# parksharks_board.net
KiCad netlist of a schematic drawn in EAGLE
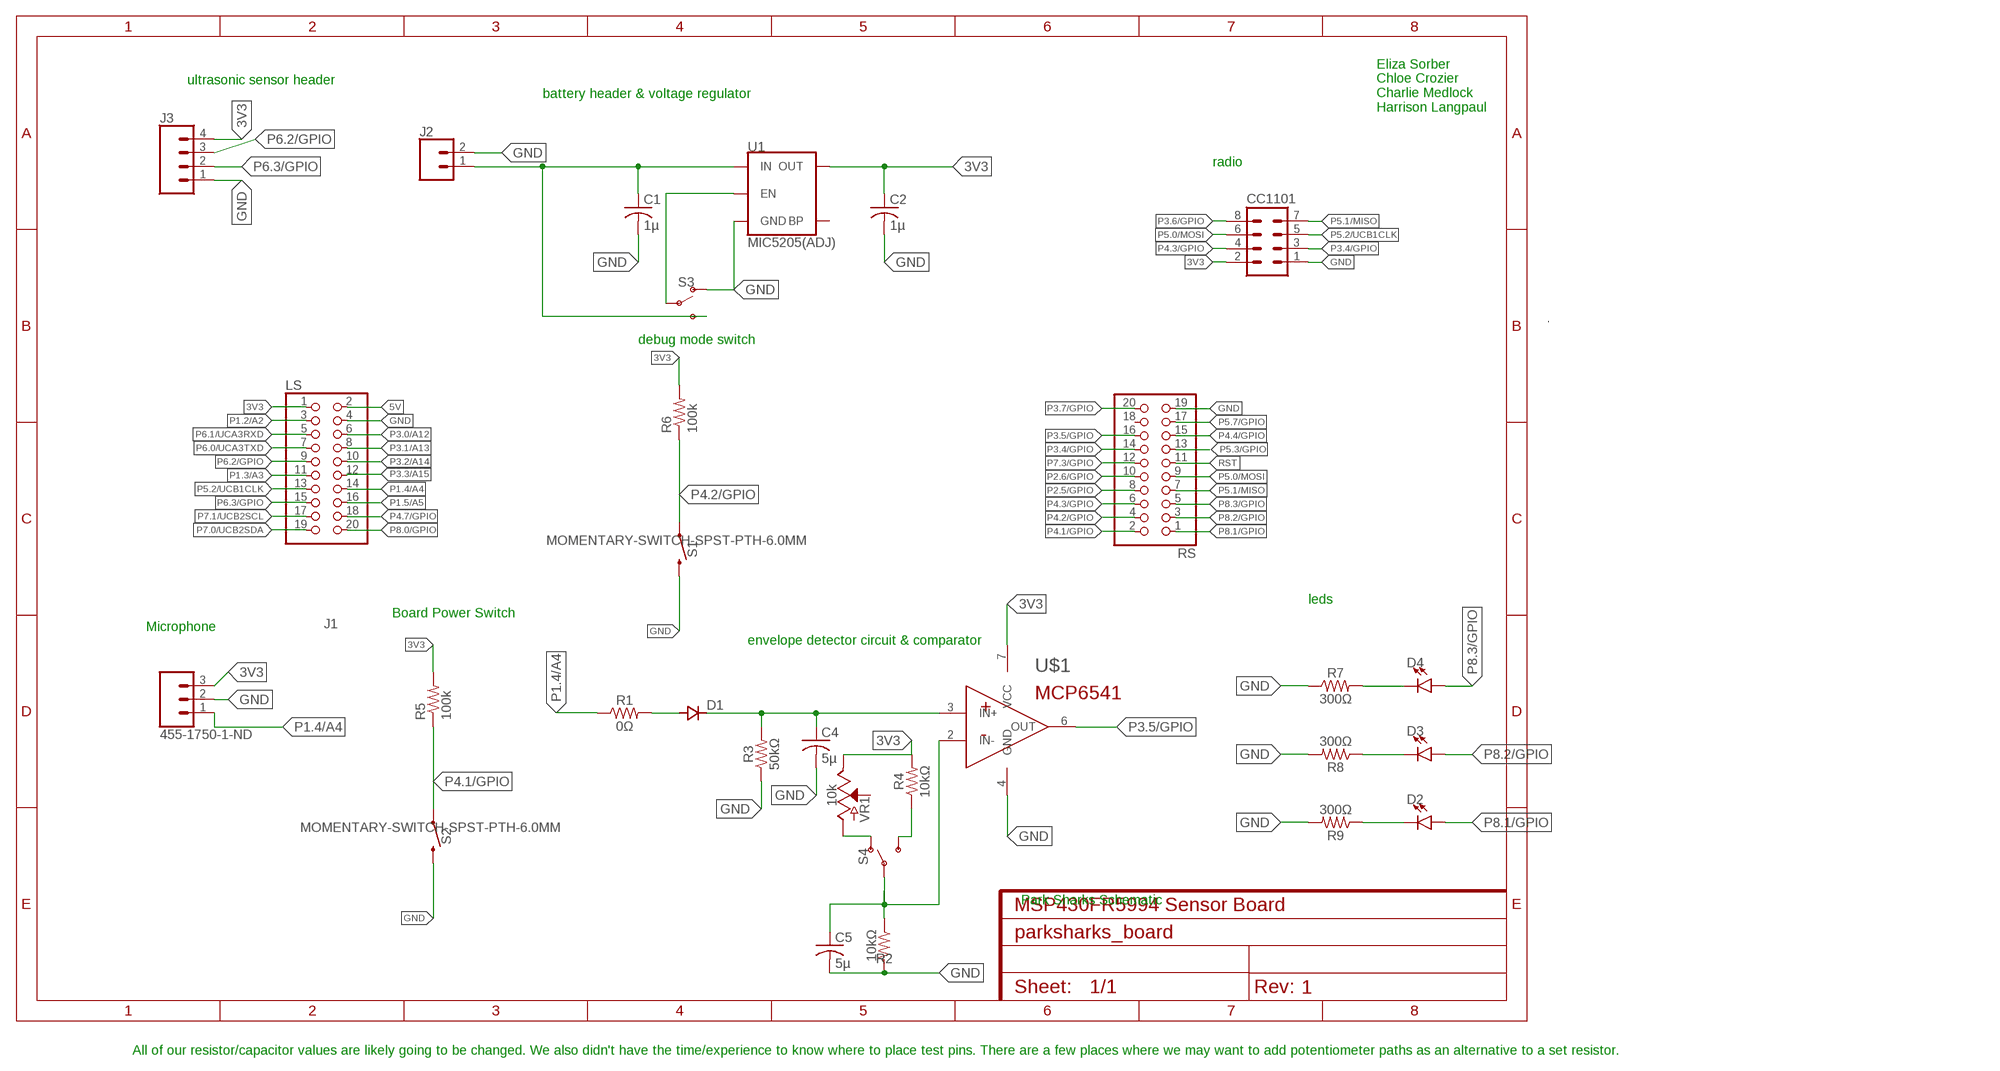
[diagram p0: schematic, sheet 1]

(export (version "E")
  (design (tool "Eeschema 10.0.6"))
  (components
    (comp (ref "C1")
      (value "1µ")
      (footprint "eagle-import:C0805")
      (libsource (lib "eagle-import") (part "C-USC0805"))
    )
    (comp (ref "C2")
      (value "1µ")
      (footprint "eagle-import:C0805")
      (libsource (lib "eagle-import") (part "C-USC0805"))
    )
    (comp (ref "C4")
      (value "5µ")
      (footprint "eagle-import:C0805")
      (libsource (lib "eagle-import") (part "C-USC0805"))
    )
    (comp (ref "C5")
      (value "5µ")
      (footprint "eagle-import:C0805")
      (libsource (lib "eagle-import") (part "C-USC0805"))
    )
    (comp (ref "CC1101")
      (value "MA04-2")
      (footprint "eagle-import:MA04-2")
      (libsource (lib "eagle-import") (part "MA04-2"))
    )
    (comp (ref "D1")
      (value "DSOD323")
      (footprint "eagle-import:SOD323")
      (fields (field (name "MPN") "CDSOD323-T05C"))
      (libsource (lib "eagle-import") (part "DSOD323"))
    )
    (comp (ref "D2")
      (value "LED5MM")
      (footprint "eagle-import:LED_5MM")
      (libsource (lib "eagle-import") (part "LED5MM"))
    )
    (comp (ref "D3")
      (value "LED5MM")
      (footprint "eagle-import:LED_5MM")
      (libsource (lib "eagle-import") (part "LED5MM"))
    )
    (comp (ref "D4")
      (value "LED5MM")
      (footprint "eagle-import:LED_5MM")
      (libsource (lib "eagle-import") (part "LED5MM"))
    )
    (comp (ref "J1")
      (value "455-1750-1-ND")
      (footprint "eagle-import:1X03")
      (libsource (lib "eagle-import") (part "CONN_03"))
    )
    (comp (ref "J2")
      (value "CONN_02")
      (footprint "eagle-import:1X02")
      (libsource (lib "eagle-import") (part "CONN_02"))
    )
    (comp (ref "J3")
      (value "CONN_04JST-PTH")
      (footprint "eagle-import:JST-4-PTH")
      (libsource (lib "eagle-import") (part "CONN_04JST-PTH"))
    )
    (comp (ref "LS")
      (value "PINHD-2X10")
      (footprint "eagle-import:2X10")
      (libsource (lib "eagle-import") (part "PINHD-2X10"))
    )
    (comp (ref "R1")
      (value "0Ω")
      (footprint "eagle-import:0805")
      (libsource (lib "eagle-import") (part "0.3OHM-0805-1/8W-1%"))
    )
    (comp (ref "R2")
      (value "10kΩ")
      (footprint "eagle-import:0805")
      (libsource (lib "eagle-import") (part "0.3OHM-0805-1/8W-1%"))
    )
    (comp (ref "R3")
      (value "50kΩ")
      (footprint "eagle-import:0805")
      (libsource (lib "eagle-import") (part "0.3OHM-0805-1/8W-1%"))
    )
    (comp (ref "R4")
      (value "10kΩ")
      (footprint "eagle-import:0805")
      (libsource (lib "eagle-import") (part "0.3OHM-0805-1/8W-1%"))
    )
    (comp (ref "R5")
      (value "100k")
      (footprint "eagle-import:R0805")
      (libsource (lib "eagle-import") (part "R-US_R0805"))
    )
    (comp (ref "R6")
      (value "100k")
      (footprint "eagle-import:R0805")
      (libsource (lib "eagle-import") (part "R-US_R0805"))
    )
    (comp (ref "R7")
      (value "300Ω")
      (footprint "eagle-import:0805")
      (libsource (lib "eagle-import") (part "0.3OHM-0805-1/8W-1%"))
    )
    (comp (ref "R8")
      (value "300Ω")
      (footprint "eagle-import:0805")
      (libsource (lib "eagle-import") (part "0.3OHM-0805-1/8W-1%"))
    )
    (comp (ref "R9")
      (value "300Ω")
      (footprint "eagle-import:0805")
      (libsource (lib "eagle-import") (part "0.3OHM-0805-1/8W-1%"))
    )
    (comp (ref "RS")
      (value "PINHD-2X10")
      (footprint "eagle-import:2X10")
      (libsource (lib "eagle-import") (part "PINHD-2X10"))
    )
    (comp (ref "S1")
      (value "MOMENTARY-SWITCH-SPST-PTH-6.0MM")
      (footprint "eagle-import:TACTILE_SWITCH_PTH_6.0MM")
      (libsource (lib "eagle-import") (part "MOMENTARY-SWITCH-SPST-PTH-6.0MM"))
    )
    (comp (ref "S2")
      (value "MOMENTARY-SWITCH-SPST-PTH-6.0MM")
      (footprint "eagle-import:TACTILE_SWITCH_PTH_6.0MM")
      (libsource (lib "eagle-import") (part "MOMENTARY-SWITCH-SPST-PTH-6.0MM"))
    )
    (comp (ref "S3")
      (value "SWITCH-SPDT-PTH-11.6X4.0MM")
      (footprint "eagle-import:SWITCH_SPDT_PTH_11.6X4.0MM")
      (libsource (lib "eagle-import") (part "SWITCH-SPDT-PTH-11.6X4.0MM"))
    )
    (comp (ref "S4")
      (value "SWITCH-SPDT-PTH-11.6X4.0MM")
      (footprint "eagle-import:SWITCH_SPDT_PTH_11.6X4.0MM")
      (libsource (lib "eagle-import") (part "SWITCH-SPDT-PTH-11.6X4.0MM"))
    )
    (comp (ref "U$1")
      (value "MCP654!")
      (footprint "eagle-import:DIP08")
      (libsource (lib "eagle-import") (part "MCP654!"))
    )
    (comp (ref "U1")
      (value "MIC5205(ADJ)")
      (footprint "eagle-import:SOT23-5")
      (libsource (lib "eagle-import") (part "V_REG_MIC5205ADJ"))
    )
    (comp (ref "VR1")
      (value "10k")
      (footprint "eagle-import:POT-PTH-ALPS")
      (libsource (lib "eagle-import") (part "POTENTIOMETER-PTH-9MM-1/20W-20%"))
    )
  )
  (nets
    (net (code "1") (name "3V3") (class "Default")
      (node (ref "C2") (pin "1") (pinfunction "1_1") (pintype "passive"))
      (node (ref "CC1101") (pin "2") (pinfunction "2_2") (pintype "passive"))
      (node (ref "J1") (pin "3") (pinfunction "3_3") (pintype "passive"))
      (node (ref "J3") (pin "4") (pinfunction "4_4") (pintype "passive"))
      (node (ref "LS") (pin "1") (pinfunction "1_1") (pintype "passive"))
      (node (ref "R4") (pin "2") (pinfunction "2_2") (pintype "passive"))
      (node (ref "R5") (pin "2") (pinfunction "2_2") (pintype "passive"))
      (node (ref "R6") (pin "2") (pinfunction "2_2") (pintype "passive"))
      (node (ref "U$1") (pin "7") (pinfunction "VCC_7") (pintype "bidirectional"))
      (node (ref "U1") (pin "5") (pinfunction "OUT_5") (pintype "passive"))
      (node (ref "VR1") (pin "P$1") (pinfunction "E_P$1") (pintype "passive"))
    )
    (net (code "2") (name "5V") (class "Default")
      (node (ref "LS") (pin "2") (pinfunction "2_2") (pintype "passive"))
    )
    (net (code "3") (name "GND") (class "Default")
      (node (ref "C1") (pin "2") (pinfunction "2_2") (pintype "passive"))
      (node (ref "C2") (pin "2") (pinfunction "2_2") (pintype "passive"))
      (node (ref "C4") (pin "2") (pinfunction "2_2") (pintype "passive"))
      (node (ref "C5") (pin "2") (pinfunction "2_2") (pintype "passive"))
      (node (ref "CC1101") (pin "1") (pinfunction "1_1") (pintype "passive"))
      (node (ref "J1") (pin "2") (pinfunction "2_2") (pintype "passive"))
      (node (ref "J2") (pin "2") (pinfunction "2_2") (pintype "passive"))
      (node (ref "J3") (pin "1") (pinfunction "1_1") (pintype "passive"))
      (node (ref "LS") (pin "4") (pinfunction "4_4") (pintype "passive"))
      (node (ref "R2") (pin "2") (pinfunction "2_2") (pintype "passive"))
      (node (ref "R3") (pin "1") (pinfunction "1_1") (pintype "passive"))
      (node (ref "R7") (pin "1") (pinfunction "1_1") (pintype "passive"))
      (node (ref "R8") (pin "2") (pinfunction "2_2") (pintype "passive"))
      (node (ref "R9") (pin "2") (pinfunction "2_2") (pintype "passive"))
      (node (ref "RS") (pin "19") (pinfunction "19_19") (pintype "passive"))
      (node (ref "S1") (pin "3") (pinfunction "2_3") (pintype "passive"))
      (node (ref "S2") (pin "3") (pinfunction "2_3") (pintype "passive"))
      (node (ref "S3") (pin "1") (pinfunction "O_1") (pintype "passive"))
      (node (ref "U$1") (pin "4") (pinfunction "GND_4") (pintype "bidirectional"))
      (node (ref "U1") (pin "2") (pinfunction "GND_2") (pintype "input"))
    )
    (net (code "4") (name "Net-(D1-A)") (class "Default")
      (node (ref "D1") (pin "2") (pinfunction "A_2") (pintype "passive"))
      (node (ref "R1") (pin "2") (pinfunction "2_2") (pintype "passive"))
    )
    (net (code "5") (name "Net-(D1-C)") (class "Default")
      (node (ref "C4") (pin "1") (pinfunction "1_1") (pintype "passive"))
      (node (ref "D1") (pin "1") (pinfunction "C_1") (pintype "passive"))
      (node (ref "R3") (pin "2") (pinfunction "2_2") (pintype "passive"))
      (node (ref "U$1") (pin "3") (pinfunction "IN+_3") (pintype "bidirectional"))
    )
    (net (code "6") (name "Net-(D2-C)") (class "Default")
      (node (ref "D2") (pin "K") (pinfunction "C_K") (pintype "passive"))
      (node (ref "R9") (pin "1") (pinfunction "1_1") (pintype "passive"))
    )
    (net (code "7") (name "Net-(D3-C)") (class "Default")
      (node (ref "D3") (pin "K") (pinfunction "C_K") (pintype "passive"))
      (node (ref "R8") (pin "1") (pinfunction "1_1") (pintype "passive"))
    )
    (net (code "8") (name "Net-(D4-C)") (class "Default")
      (node (ref "D4") (pin "K") (pinfunction "C_K") (pintype "passive"))
      (node (ref "R7") (pin "2") (pinfunction "2_2") (pintype "passive"))
    )
    (net (code "9") (name "Net-(S3-P)") (class "Default")
      (node (ref "S3") (pin "2") (pinfunction "P_2") (pintype "passive"))
      (node (ref "U1") (pin "3") (pinfunction "EN_3") (pintype "input"))
    )
    (net (code "10") (name "Net-(S3-S)") (class "Default")
      (node (ref "C1") (pin "1") (pinfunction "1_1") (pintype "passive"))
      (node (ref "J2") (pin "1") (pinfunction "1_1") (pintype "passive"))
      (node (ref "S3") (pin "3") (pinfunction "S_3") (pintype "passive"))
      (node (ref "U1") (pin "1") (pinfunction "IN_1") (pintype "input"))
    )
    (net (code "11") (name "Net-(S4-O)") (class "Default")
      (node (ref "S4") (pin "1") (pinfunction "O_1") (pintype "passive"))
      (node (ref "VR1") (pin "P$3") (pinfunction "A_P$3") (pintype "passive"))
    )
    (net (code "12") (name "Net-(S4-P)") (class "Default")
      (node (ref "C5") (pin "1") (pinfunction "1_1") (pintype "passive"))
      (node (ref "R2") (pin "1") (pinfunction "1_1") (pintype "passive"))
      (node (ref "S4") (pin "2") (pinfunction "P_2") (pintype "passive"))
      (node (ref "U$1") (pin "2") (pinfunction "IN-_2") (pintype "bidirectional"))
    )
    (net (code "13") (name "Net-(S4-S)") (class "Default")
      (node (ref "R4") (pin "1") (pinfunction "1_1") (pintype "passive"))
      (node (ref "S4") (pin "3") (pinfunction "S_3") (pintype "passive"))
    )
    (net (code "14") (name "P1.2{slash}A2") (class "Default")
      (node (ref "LS") (pin "3") (pinfunction "3_3") (pintype "passive"))
    )
    (net (code "15") (name "P1.3{slash}A3") (class "Default")
      (node (ref "LS") (pin "11") (pinfunction "11_11") (pintype "passive"))
    )
    (net (code "16") (name "P1.4{slash}A4") (class "Default")
      (node (ref "J1") (pin "1") (pinfunction "1_1") (pintype "passive"))
      (node (ref "LS") (pin "14") (pinfunction "14_14") (pintype "passive"))
      (node (ref "R1") (pin "1") (pinfunction "1_1") (pintype "passive"))
    )
    (net (code "17") (name "P1.5{slash}A5") (class "Default")
      (node (ref "LS") (pin "16") (pinfunction "16_16") (pintype "passive"))
    )
    (net (code "18") (name "P2.5{slash}GPIO") (class "Default")
      (node (ref "RS") (pin "8") (pinfunction "8_8") (pintype "passive"))
    )
    (net (code "19") (name "P2.6{slash}GPIO") (class "Default")
      (node (ref "RS") (pin "10") (pinfunction "10_10") (pintype "passive"))
    )
    (net (code "20") (name "P3.0{slash}A12") (class "Default")
      (node (ref "LS") (pin "6") (pinfunction "6_6") (pintype "passive"))
    )
    (net (code "21") (name "P3.1{slash}A13") (class "Default")
      (node (ref "LS") (pin "8") (pinfunction "8_8") (pintype "passive"))
    )
    (net (code "22") (name "P3.2{slash}A14") (class "Default")
      (node (ref "LS") (pin "10") (pinfunction "10_10") (pintype "passive"))
    )
    (net (code "23") (name "P3.3{slash}A15") (class "Default")
      (node (ref "LS") (pin "12") (pinfunction "12_12") (pintype "passive"))
    )
    (net (code "24") (name "P3.4{slash}GPIO") (class "Default")
      (node (ref "CC1101") (pin "3") (pinfunction "3_3") (pintype "passive"))
      (node (ref "RS") (pin "14") (pinfunction "14_14") (pintype "passive"))
    )
    (net (code "25") (name "P3.5{slash}GPIO") (class "Default")
      (node (ref "RS") (pin "16") (pinfunction "16_16") (pintype "passive"))
      (node (ref "U$1") (pin "6") (pinfunction "OUT_6") (pintype "bidirectional"))
    )
    (net (code "26") (name "P3.6{slash}GPIO") (class "Default")
      (node (ref "CC1101") (pin "8") (pinfunction "8_8") (pintype "passive"))
    )
    (net (code "27") (name "P3.7{slash}GPIO") (class "Default")
      (node (ref "RS") (pin "20") (pinfunction "20_20") (pintype "passive"))
    )
    (net (code "28") (name "P4.1{slash}GPIO") (class "Default")
      (node (ref "R5") (pin "1") (pinfunction "1_1") (pintype "passive"))
      (node (ref "RS") (pin "2") (pinfunction "2_2") (pintype "passive"))
      (node (ref "S2") (pin "1") (pinfunction "1_1") (pintype "passive"))
    )
    (net (code "29") (name "P4.2{slash}GPIO") (class "Default")
      (node (ref "R6") (pin "1") (pinfunction "1_1") (pintype "passive"))
      (node (ref "RS") (pin "4") (pinfunction "4_4") (pintype "passive"))
      (node (ref "S1") (pin "1") (pinfunction "1_1") (pintype "passive"))
    )
    (net (code "30") (name "P4.3{slash}GPIO") (class "Default")
      (node (ref "CC1101") (pin "4") (pinfunction "4_4") (pintype "passive"))
      (node (ref "RS") (pin "6") (pinfunction "6_6") (pintype "passive"))
    )
    (net (code "31") (name "P4.4{slash}GPIO") (class "Default")
      (node (ref "RS") (pin "15") (pinfunction "15_15") (pintype "passive"))
    )
    (net (code "32") (name "P4.7{slash}GPIO") (class "Default")
      (node (ref "LS") (pin "18") (pinfunction "18_18") (pintype "passive"))
    )
    (net (code "33") (name "P5.0{slash}MOSI") (class "Default")
      (node (ref "CC1101") (pin "6") (pinfunction "6_6") (pintype "passive"))
      (node (ref "RS") (pin "9") (pinfunction "9_9") (pintype "passive"))
    )
    (net (code "34") (name "P5.1{slash}MISO") (class "Default")
      (node (ref "CC1101") (pin "7") (pinfunction "7_7") (pintype "passive"))
      (node (ref "RS") (pin "7") (pinfunction "7_7") (pintype "passive"))
    )
    (net (code "35") (name "P5.2{slash}UCB1CLK") (class "Default")
      (node (ref "CC1101") (pin "5") (pinfunction "5_5") (pintype "passive"))
      (node (ref "LS") (pin "13") (pinfunction "13_13") (pintype "passive"))
    )
    (net (code "36") (name "P5.3{slash}GPIO") (class "Default")
      (node (ref "RS") (pin "13") (pinfunction "13_13") (pintype "passive"))
    )
    (net (code "37") (name "P5.7{slash}GPIO") (class "Default")
      (node (ref "RS") (pin "17") (pinfunction "17_17") (pintype "passive"))
    )
    (net (code "38") (name "P6.0{slash}UCA3TXD") (class "Default")
      (node (ref "LS") (pin "7") (pinfunction "7_7") (pintype "passive"))
    )
    (net (code "39") (name "P6.1{slash}UCA3RXD") (class "Default")
      (node (ref "LS") (pin "5") (pinfunction "5_5") (pintype "passive"))
    )
    (net (code "40") (name "P6.2{slash}GPIO") (class "Default")
      (node (ref "J3") (pin "3") (pinfunction "3_3") (pintype "passive"))
      (node (ref "LS") (pin "9") (pinfunction "9_9") (pintype "passive"))
    )
    (net (code "41") (name "P6.3{slash}GPIO") (class "Default")
      (node (ref "J3") (pin "2") (pinfunction "2_2") (pintype "passive"))
      (node (ref "LS") (pin "15") (pinfunction "15_15") (pintype "passive"))
    )
    (net (code "42") (name "P7.0{slash}UCB2SDA") (class "Default")
      (node (ref "LS") (pin "19") (pinfunction "19_19") (pintype "passive"))
    )
    (net (code "43") (name "P7.1{slash}UCB2SCL") (class "Default")
      (node (ref "LS") (pin "17") (pinfunction "17_17") (pintype "passive"))
    )
    (net (code "44") (name "P7.3{slash}GPIO") (class "Default")
      (node (ref "RS") (pin "12") (pinfunction "12_12") (pintype "passive"))
    )
    (net (code "45") (name "P8.0{slash}GPIO") (class "Default")
      (node (ref "LS") (pin "20") (pinfunction "20_20") (pintype "passive"))
    )
    (net (code "46") (name "P8.1{slash}GPIO") (class "Default")
      (node (ref "D2") (pin "A") (pinfunction "A_A") (pintype "passive"))
      (node (ref "RS") (pin "1") (pinfunction "1_1") (pintype "passive"))
    )
    (net (code "47") (name "P8.2{slash}GPIO") (class "Default")
      (node (ref "D3") (pin "A") (pinfunction "A_A") (pintype "passive"))
      (node (ref "RS") (pin "3") (pinfunction "3_3") (pintype "passive"))
    )
    (net (code "48") (name "P8.3{slash}GPIO") (class "Default")
      (node (ref "D4") (pin "A") (pinfunction "A_A") (pintype "passive"))
      (node (ref "RS") (pin "5") (pinfunction "5_5") (pintype "passive"))
    )
    (net (code "49") (name "RST") (class "Default")
      (node (ref "RS") (pin "11") (pinfunction "11_11") (pintype "passive"))
    )
    (net (code "50") (name "unconnected-(RS-Pad18)") (class "Default")
      (node (ref "RS") (pin "18") (pinfunction "18_18") (pintype "passive"))
    )
    (net (code "51") (name "unconnected-(U1-BP-Pad4)") (class "Default")
      (node (ref "U1") (pin "4") (pinfunction "BP_4") (pintype "input"))
    )
    (net (code "52") (name "unconnected-(VR1-S-PadP$2)") (class "Default")
      (node (ref "VR1") (pin "P$2") (pinfunction "S_P$2") (pintype "passive"))
    )
  )
)
